# PCB_-_NC4040-4_0-1_0.net
KiCad netlist of a schematic drawn in EasyEDA Pro
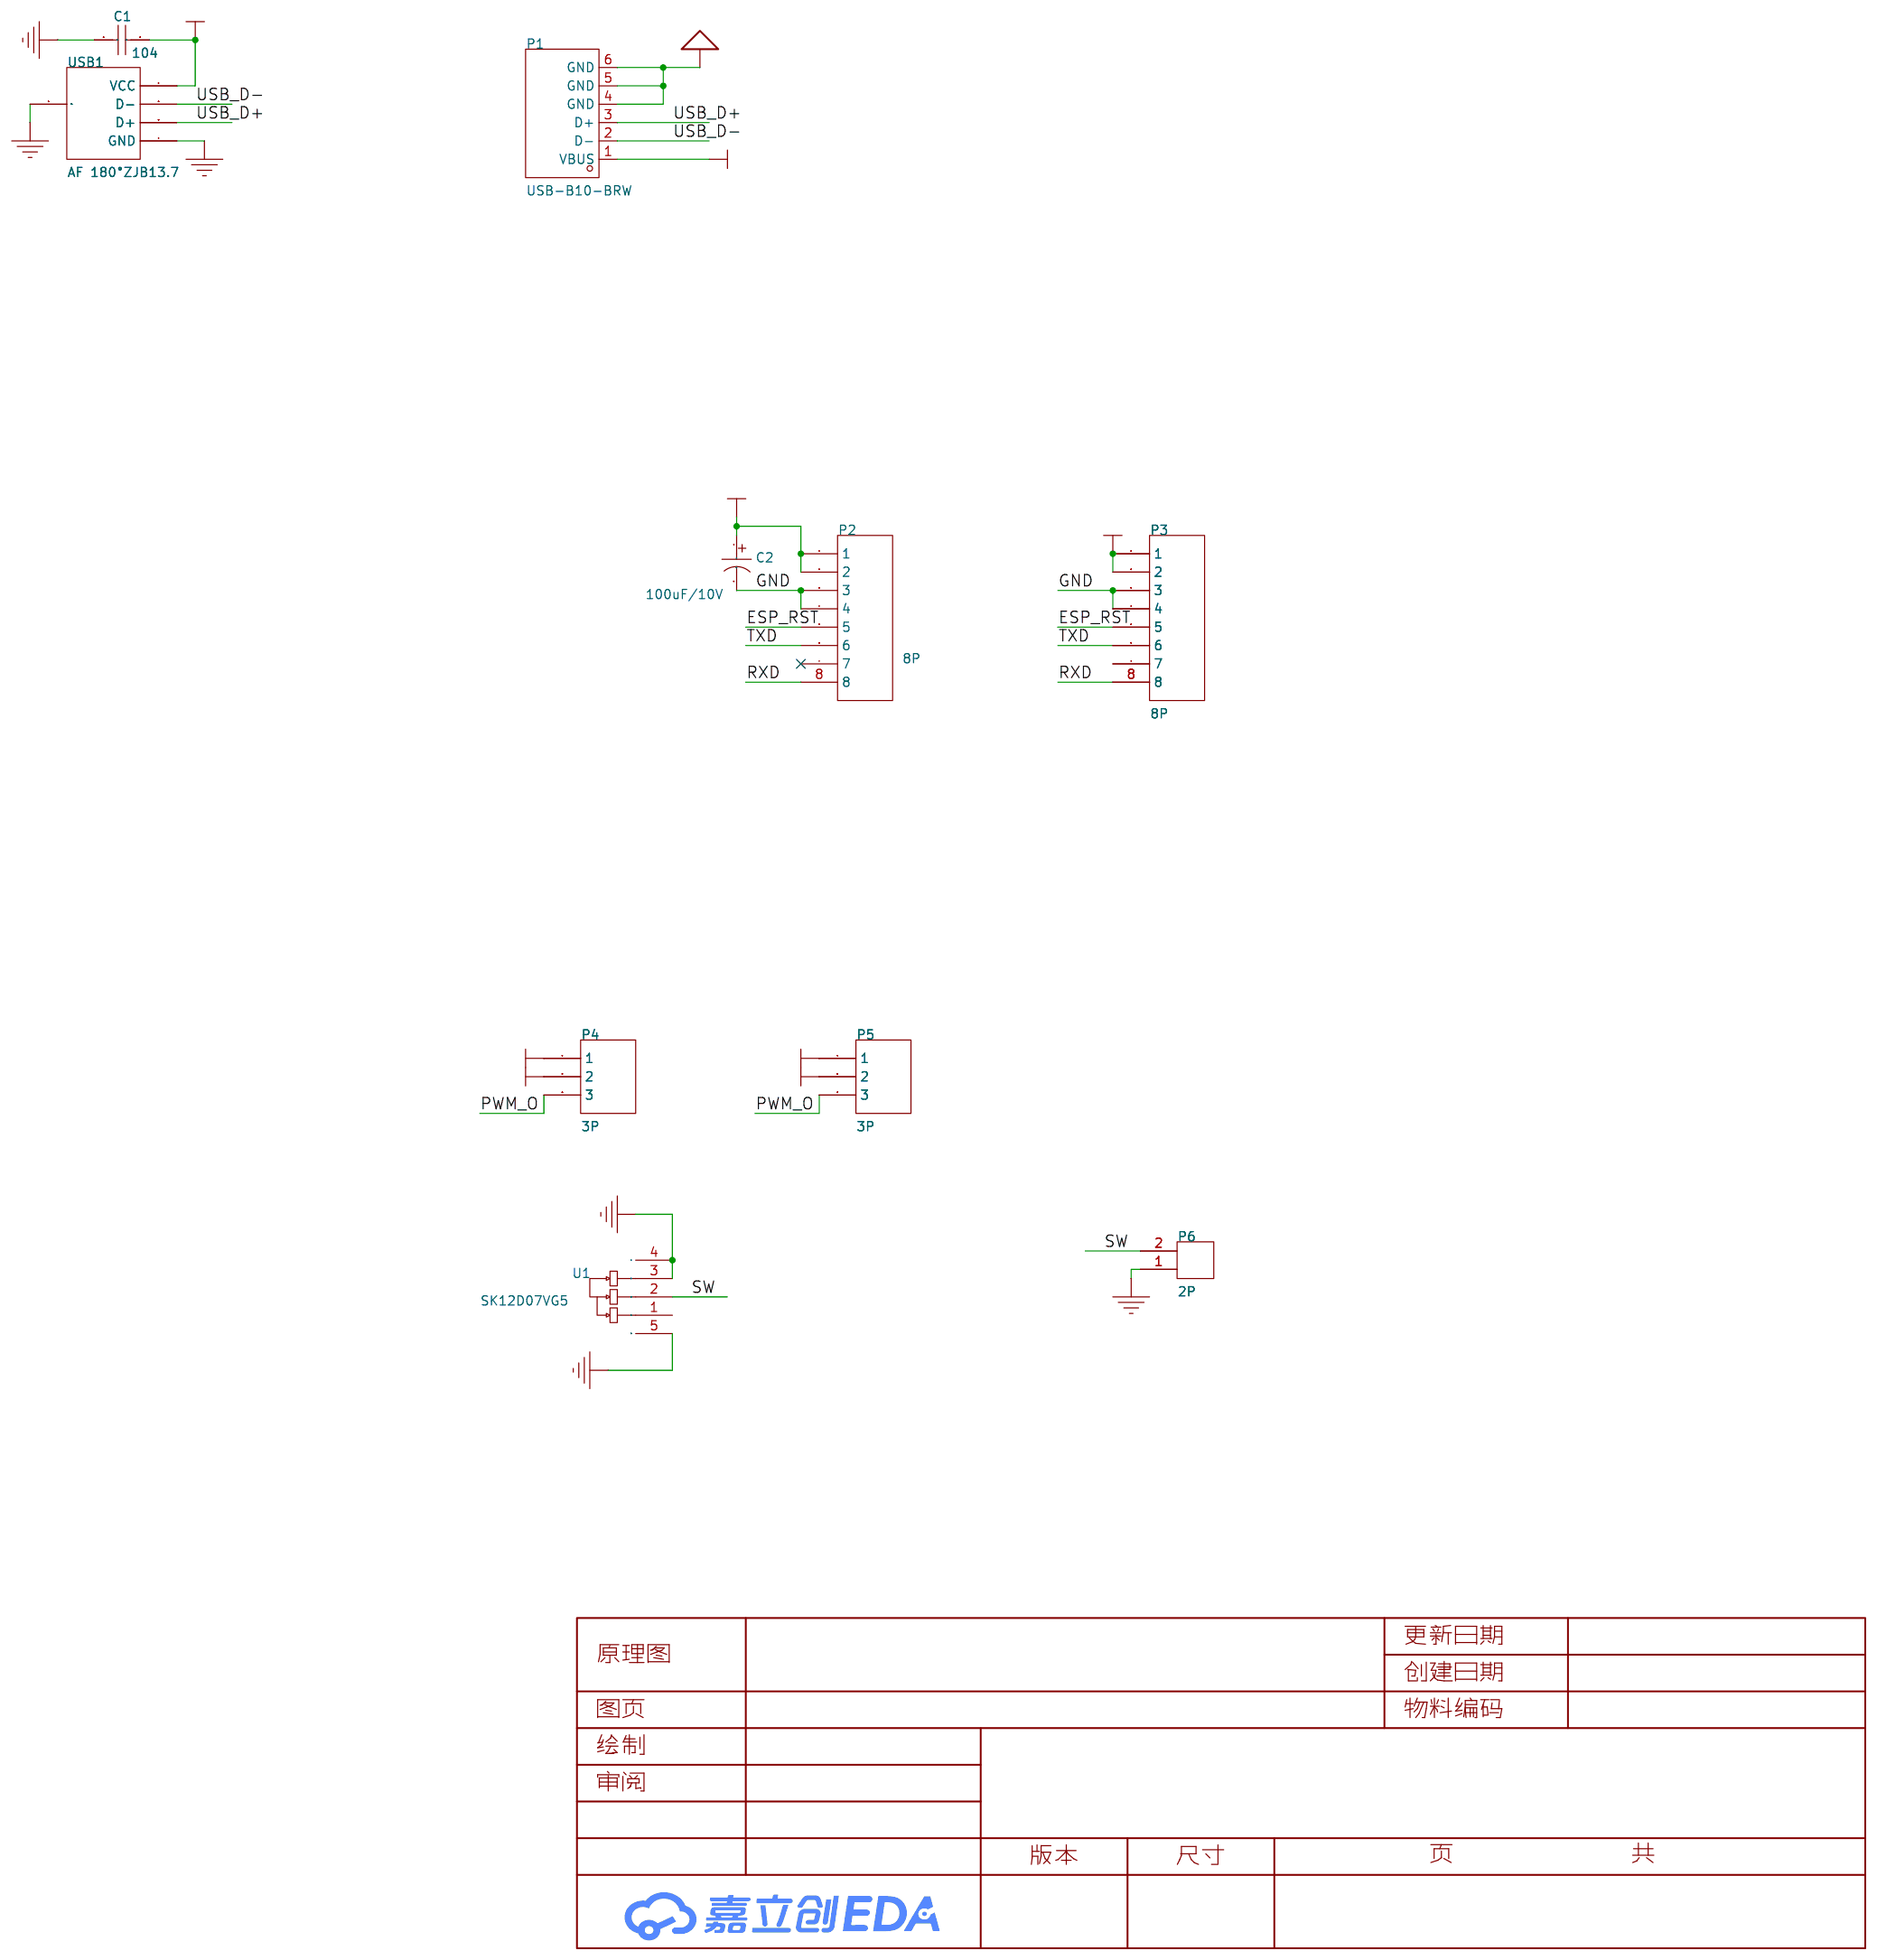
[diagram p0: schematic sheet]

(export (version "E")
  (design (tool "Eeschema 10.0.6"))
  (components
    (comp (ref "C1")
      (value "104")
      (footprint "easyedapro:0603C")
      (description "Capacitor (Semiconductor SIM Model)")
      (libsource (lib "easyedapro") (part "Cap Semi"))
    )
    (comp (ref "C2")
      (value "100uF/10V")
      (footprint "easyedapro:CAP-SMD_BD5.0-L5.3-W5.3-RD")
      (fields (field (name "Manufacturer Part") "CS1A101M-CRD54") (field (name "Manufacturer") "ST(先科)"))
      (libsource (lib "easyedapro") (part "CS1A101M-CRD54"))
    )
    (comp (ref "P1")
      (value "USB-B10-BRW")
      (footprint "easyedapro:USB-B-TH_USB-B10-BRW")
      (fields (field (name "Manufacturer") "XUNPU(讯普)"))
      (libsource (lib "easyedapro") (part "USB-B10-BRW"))
    )
    (comp (ref "P2") (value "8P") (footprint "easyedapro:IDC8") (libsource (lib "easyedapro") (part "8P")))
    (comp (ref "P3") (value "8P") (footprint "easyedapro:IDC8弯脚") (libsource (lib "easyedapro") (part "8P")))
    (comp (ref "P4")
      (value "3P")
      (footprint "easyedapro:HDR1X3_CON")
      (libsource (lib "easyedapro") (part "3P"))
    )
    (comp (ref "P5")
      (value "3P")
      (footprint "easyedapro:HDR1X3_P")
      (libsource (lib "easyedapro") (part "3P"))
    )
    (comp (ref "P6") (value "2P") (libsource (lib "easyedapro") (part "2P")))
    (comp (ref "U1")
      (value "SK12D07VG5")
      (footprint "easyedapro:SW-TH_SHOU_SK12D07VG5")
      (description "电路结构:单刀双掷;安装方式:-;开关颜色:-;额定电流:500mA;额定电压:50V;工作寿命:5千次;")
      (fields (field (name "Manufacturer") "SHOU HAN(首韩)"))
      (libsource (lib "easyedapro") (part "SK12D07VG5_C3020419"))
    )
    (comp (ref "USB1")
      (value "AF 180°ZJB13.7")
      (footprint "easyedapro:USB-A-TH_AF-ZJB13.7")
      (description "连接器类型:Type-A;标准:USB 2.0;公母:母;安装方式:直插;触点数量:4P;端口数量:1;额定电流 - 电源:1.5A;工作温度范围:-25°C~+85°C;")
      (fields (field (name "Manufacturer") "SHOU HAN(首韩)"))
      (libsource (lib "easyedapro") (part "AF 180°ZJB13.7"))
    )
  )
  (nets
    (net (code "1") (name "/ESP_RST") (class "Default")
      (node (ref "P2") (pin "5") (pinfunction "5_5") (pintype "unspecified"))
      (node (ref "P3") (pin "5") (pinfunction "5_5") (pintype "unspecified"))
    )
    (net (code "2") (name "/PWM_O") (class "Default")
      (node (ref "P4") (pin "3") (pinfunction "3_3") (pintype "unspecified"))
      (node (ref "P5") (pin "3") (pinfunction "3_3") (pintype "unspecified"))
    )
    (net (code "3") (name "/RXD") (class "Default")
      (node (ref "P2") (pin "8") (pinfunction "8_8") (pintype "unspecified"))
      (node (ref "P3") (pin "8") (pinfunction "8_8") (pintype "unspecified"))
    )
    (net (code "4") (name "/SW") (class "Default")
      (node (ref "P6") (pin "2") (pintype "input"))
      (node (ref "U1") (pin "2") (pinfunction "2_2") (pintype "unspecified"))
    )
    (net (code "5") (name "/TXD") (class "Default")
      (node (ref "P2") (pin "6") (pinfunction "6_6") (pintype "unspecified"))
      (node (ref "P3") (pin "6") (pinfunction "6_6") (pintype "unspecified"))
    )
    (net (code "6") (name "/USB_D+") (class "Default")
      (node (ref "P1") (pin "3") (pinfunction "D+_3") (pintype "unspecified"))
      (node (ref "USB1") (pin "3") (pinfunction "D+_3") (pintype "input"))
    )
    (net (code "7") (name "/USB_D-") (class "Default")
      (node (ref "P1") (pin "2") (pinfunction "D-_2") (pintype "unspecified"))
      (node (ref "USB1") (pin "2") (pinfunction "D-_2") (pintype "input"))
    )
    (net (code "8") (name "5V_VCC") (class "Default")
      (node (ref "C2") (pin "1") (pinfunction "1_1") (pintype "input"))
      (node (ref "P2") (pin "1") (pinfunction "1_1") (pintype "unspecified"))
      (node (ref "P2") (pin "2") (pinfunction "2_2") (pintype "unspecified"))
      (node (ref "P3") (pin "1") (pinfunction "1_1") (pintype "unspecified"))
      (node (ref "P3") (pin "2") (pinfunction "2_2") (pintype "unspecified"))
    )
    (net (code "9") (name "24V") (class "Default")
      (node (ref "P4") (pin "1") (pinfunction "1_1") (pintype "unspecified"))
      (node (ref "P5") (pin "1") (pinfunction "1_1") (pintype "unspecified"))
    )
    (net (code "10") (name "GND") (class "Default")
      (node (ref "C1") (pin "2") (pinfunction "2_2") (pintype "unspecified"))
      (node (ref "C2") (pin "2") (pinfunction "2_2") (pintype "input"))
      (node (ref "P1") (pin "4") (pinfunction "GND_4") (pintype "unspecified"))
      (node (ref "P1") (pin "5") (pinfunction "GND_5") (pintype "unspecified"))
      (node (ref "P1") (pin "6") (pinfunction "GND_6") (pintype "unspecified"))
      (node (ref "P2") (pin "3") (pinfunction "3_3") (pintype "unspecified"))
      (node (ref "P2") (pin "4") (pinfunction "4_4") (pintype "unspecified"))
      (node (ref "P3") (pin "3") (pinfunction "3_3") (pintype "unspecified"))
      (node (ref "P3") (pin "4") (pinfunction "4_4") (pintype "unspecified"))
      (node (ref "P4") (pin "2") (pinfunction "2_2") (pintype "unspecified"))
      (node (ref "P5") (pin "2") (pinfunction "2_2") (pintype "unspecified"))
      (node (ref "P6") (pin "1") (pintype "input"))
      (node (ref "U1") (pin "3") (pinfunction "3_3") (pintype "unspecified"))
      (node (ref "U1") (pin "4") (pinfunction "4_4") (pintype "unspecified"))
      (node (ref "U1") (pin "5") (pinfunction "5_5") (pintype "unspecified"))
      (node (ref "USB1") (pin "4") (pinfunction "GND_4") (pintype "input"))
      (node (ref "USB1") (pin "5") (pinfunction "SHLD_5") (pintype "unspecified"))
    )
    (net (code "11") (name "VUSB") (class "Default")
      (node (ref "C1") (pin "1") (pinfunction "1_1") (pintype "unspecified"))
      (node (ref "P1") (pin "1") (pinfunction "VBUS_1") (pintype "unspecified"))
      (node (ref "USB1") (pin "1") (pinfunction "VCC_1") (pintype "input"))
    )
    (net (code "12") (name "unconnected-(P2-Pad7)") (class "Default")
      (node (ref "P2") (pin "7") (pinfunction "7_7") (pintype "unspecified+no_connect"))
    )
    (net (code "13") (name "unconnected-(P3-Pad7)") (class "Default")
      (node (ref "P3") (pin "7") (pinfunction "7_7") (pintype "unspecified"))
    )
    (net (code "14") (name "unconnected-(U1-Pad1)") (class "Default")
      (node (ref "U1") (pin "1") (pinfunction "1_1") (pintype "unspecified"))
    )
  )
)
